# nrfxiao.net
KiCad netlist of a schematic drawn in EAGLE
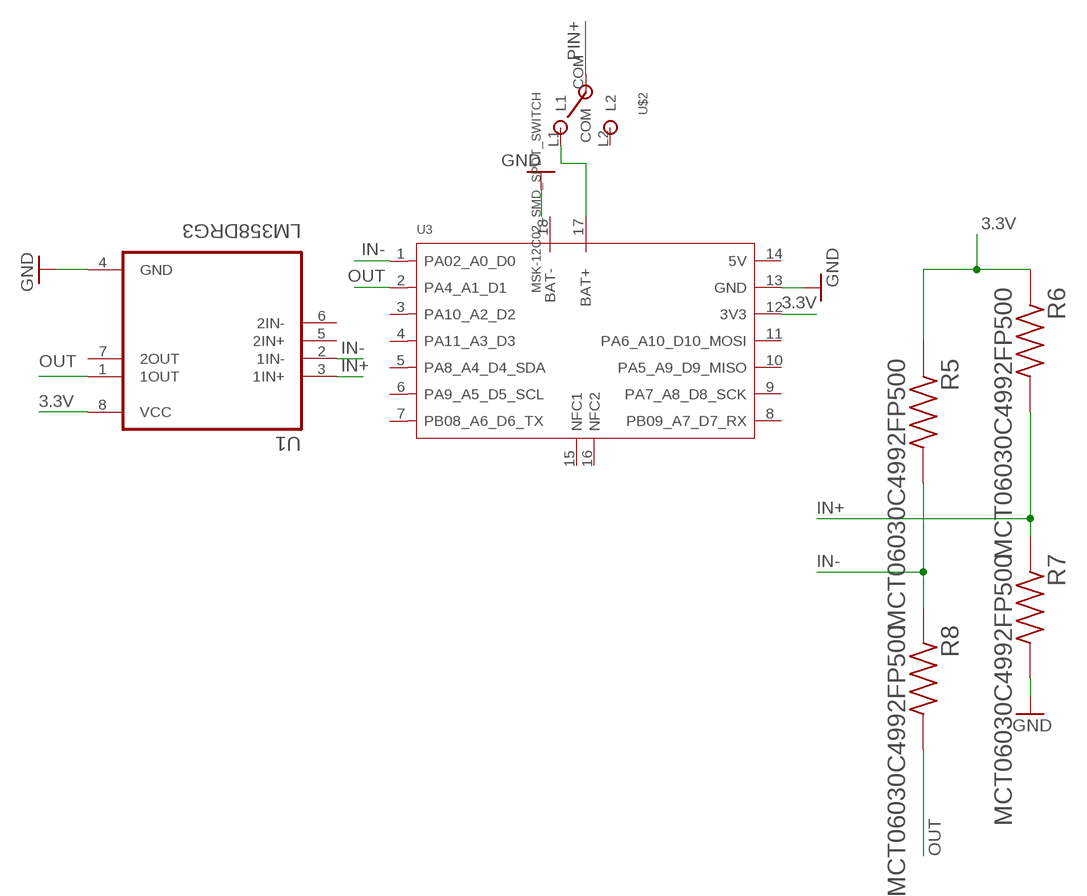
[diagram p0: schematic, sheet 1]

(export (version "E")
  (design (tool "Eeschema 10.0.6"))
  (components
    (comp (ref "R5")
      (value "MCT06030C4992FP500")
      (footprint "eagle-import:RESC1508X55N")
      (fields (field (name "MF") "Vishay Beyschlag"))
      (libsource (lib "eagle-import") (part "MCT06030C4992FP500"))
    )
    (comp (ref "R6")
      (value "MCT06030C4992FP500")
      (footprint "eagle-import:RESC1508X55N")
      (fields (field (name "MF") "Vishay Beyschlag"))
      (libsource (lib "eagle-import") (part "MCT06030C4992FP500"))
    )
    (comp (ref "R7")
      (value "MCT06030C4992FP500")
      (footprint "eagle-import:RESC1508X55N")
      (fields (field (name "MF") "Vishay Beyschlag"))
      (libsource (lib "eagle-import") (part "MCT06030C4992FP500"))
    )
    (comp (ref "R8")
      (value "MCT06030C4992FP500")
      (footprint "eagle-import:RESC1508X55N")
      (fields (field (name "MF") "Vishay Beyschlag"))
      (libsource (lib "eagle-import") (part "MCT06030C4992FP500"))
    )
    (comp (ref "U$2")
      (value "MSK-12C02_SMD_SPDT_SWITCH")
      (footprint "eagle-import:MSK-12C02")
      (libsource (lib "eagle-import") (part "MSK-12C02_SMD_SPDT_SWITCH"))
    )
    (comp (ref "U1")
      (value "LM358DRG3")
      (footprint "eagle-import:SOIC127P599X175-8N")
      (fields (field (name "MF") "Texas Instruments"))
      (libsource (lib "eagle-import") (part "LM358DRG3"))
    )
    (comp (ref "U3")
      (value "MOUDLE-SEEEDUINO-XIAO-NRF52840-SENSE-SMD")
      (footprint "eagle-import:MOUDLE16P-SMD-2.54-21X17.8MM")
      (libsource (lib "eagle-import") (part "MOUDLE-SEEEDUINO-XIAO-NRF52840-SENSE-SMD"))
    )
  )
  (nets
    (net (code "1") (name "/3.3V") (class "Default")
      (node (ref "R5") (pin "1") (pinfunction "1_1") (pintype "passive"))
      (node (ref "R6") (pin "1") (pinfunction "1_1") (pintype "passive"))
      (node (ref "U1") (pin "8") (pinfunction "VCC_8") (pintype "power_in"))
      (node (ref "U3") (pin "12") (pinfunction "3V3_12") (pintype "bidirectional"))
    )
    (net (code "2") (name "/IN+") (class "Default")
      (node (ref "R6") (pin "2") (pinfunction "2_2") (pintype "passive"))
      (node (ref "R7") (pin "1") (pinfunction "1_1") (pintype "passive"))
      (node (ref "U1") (pin "3") (pinfunction "1IN+_3") (pintype "input"))
    )
    (net (code "3") (name "/IN-") (class "Default")
      (node (ref "R5") (pin "2") (pinfunction "2_2") (pintype "passive"))
      (node (ref "R8") (pin "1") (pinfunction "1_1") (pintype "passive"))
      (node (ref "U1") (pin "2") (pinfunction "1IN-_2") (pintype "input"))
      (node (ref "U3") (pin "1") (pinfunction "PA02_A0_D0_1") (pintype "bidirectional"))
    )
    (net (code "4") (name "/OUT") (class "Default")
      (node (ref "R8") (pin "2") (pinfunction "2_2") (pintype "passive"))
      (node (ref "U1") (pin "1") (pinfunction "1OUT_1") (pintype "output"))
      (node (ref "U3") (pin "2") (pinfunction "PA4_A1_D1_2") (pintype "bidirectional"))
    )
    (net (code "5") (name "/PIN+") (class "Default")
      (node (ref "U$2") (pin "COM") (pinfunction "COM_COM") (pintype "bidirectional"))
    )
    (net (code "6") (name "GND") (class "Default")
      (node (ref "R7") (pin "2") (pinfunction "2_2") (pintype "passive"))
      (node (ref "U1") (pin "4") (pinfunction "GND_4") (pintype "power_in"))
      (node (ref "U3") (pin "13") (pinfunction "GND_13") (pintype "bidirectional"))
    )
    (net (code "7") (name "Net-(U3-BAT+)") (class "Default")
      (node (ref "U$2") (pin "L1") (pinfunction "L1_L1") (pintype "bidirectional"))
      (node (ref "U3") (pin "17") (pinfunction "BAT+_17") (pintype "bidirectional"))
    )
    (net (code "8") (name "unconnected-(U$2-PadL2)") (class "Default")
      (node (ref "U$2") (pin "L2") (pinfunction "L2_L2") (pintype "bidirectional"))
    )
    (net (code "9") (name "unconnected-(U1-2IN+-Pad5)") (class "Default")
      (node (ref "U1") (pin "5") (pinfunction "2IN+_5") (pintype "input"))
    )
    (net (code "10") (name "unconnected-(U1-2IN--Pad6)") (class "Default")
      (node (ref "U1") (pin "6") (pinfunction "2IN-_6") (pintype "input"))
    )
    (net (code "11") (name "unconnected-(U1-2OUT-Pad7)") (class "Default")
      (node (ref "U1") (pin "7") (pinfunction "2OUT_7") (pintype "output"))
    )
    (net (code "12") (name "unconnected-(U3-5V-Pad14)") (class "Default")
      (node (ref "U3") (pin "14") (pinfunction "5V_14") (pintype "bidirectional"))
    )
    (net (code "13") (name "unconnected-(U3-BAT--Pad18)") (class "Default")
      (node (ref "U3") (pin "18") (pinfunction "BAT-_18") (pintype "bidirectional"))
    )
    (net (code "14") (name "unconnected-(U3-NFC1-Pad15)") (class "Default")
      (node (ref "U3") (pin "15") (pinfunction "NFC1_15") (pintype "bidirectional"))
    )
    (net (code "15") (name "unconnected-(U3-NFC2-Pad16)") (class "Default")
      (node (ref "U3") (pin "16") (pinfunction "NFC2_16") (pintype "bidirectional"))
    )
    (net (code "16") (name "unconnected-(U3-PA5_A9_D9_MISO-Pad10)") (class "Default")
      (node (ref "U3") (pin "10") (pinfunction "PA5_A9_D9_MISO_10") (pintype "bidirectional"))
    )
    (net (code "17") (name "unconnected-(U3-PA6_A10_D10_MOSI-Pad11)") (class "Default")
      (node (ref "U3") (pin "11") (pinfunction "PA6_A10_D10_MOSI_11") (pintype "bidirectional"))
    )
    (net (code "18") (name "unconnected-(U3-PA7_A8_D8_SCK-Pad9)") (class "Default")
      (node (ref "U3") (pin "9") (pinfunction "PA7_A8_D8_SCK_9") (pintype "bidirectional"))
    )
    (net (code "19") (name "unconnected-(U3-PA8_A4_D4_SDA-Pad5)") (class "Default")
      (node (ref "U3") (pin "5") (pinfunction "PA8_A4_D4_SDA_5") (pintype "bidirectional"))
    )
    (net (code "20") (name "unconnected-(U3-PA9_A5_D5_SCL-Pad6)") (class "Default")
      (node (ref "U3") (pin "6") (pinfunction "PA9_A5_D5_SCL_6") (pintype "bidirectional"))
    )
    (net (code "21") (name "unconnected-(U3-PA10_A2_D2-Pad3)") (class "Default")
      (node (ref "U3") (pin "3") (pinfunction "PA10_A2_D2_3") (pintype "bidirectional"))
    )
    (net (code "22") (name "unconnected-(U3-PA11_A3_D3-Pad4)") (class "Default")
      (node (ref "U3") (pin "4") (pinfunction "PA11_A3_D3_4") (pintype "bidirectional"))
    )
    (net (code "23") (name "unconnected-(U3-PB08_A6_D6_TX-Pad7)") (class "Default")
      (node (ref "U3") (pin "7") (pinfunction "PB08_A6_D6_TX_7") (pintype "bidirectional"))
    )
    (net (code "24") (name "unconnected-(U3-PB09_A7_D7_RX-Pad8)") (class "Default")
      (node (ref "U3") (pin "8") (pinfunction "PB09_A7_D7_RX_8") (pintype "bidirectional"))
    )
  )
)
